# Motors.net
KiCad netlist of a schematic drawn in Altium Designer
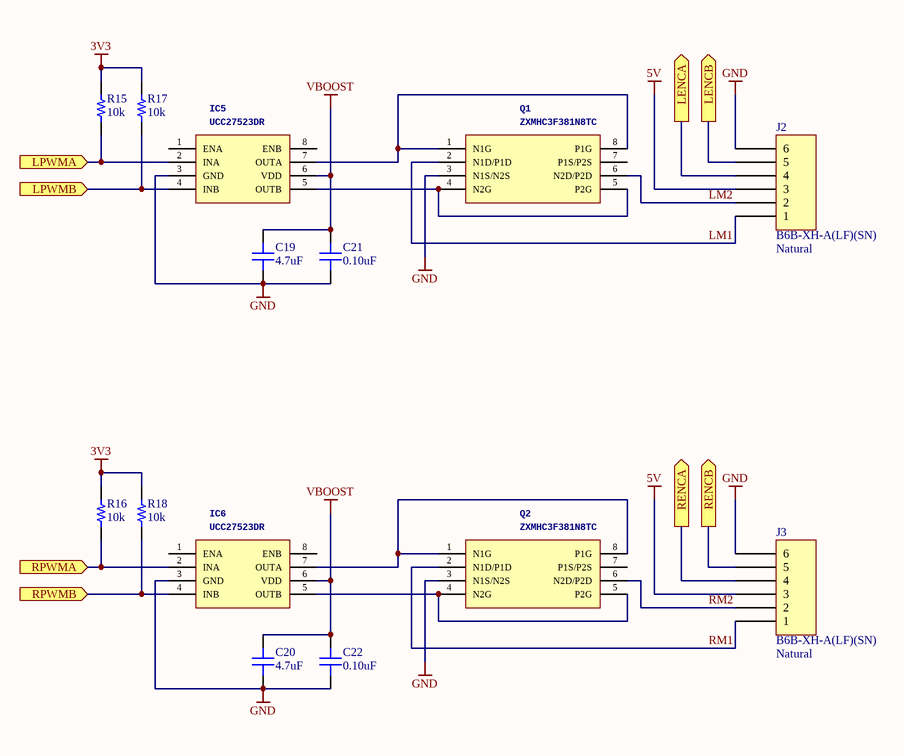
[diagram p0: Motors.SchDoc]

(export (version "E")
  (design (tool "Eeschema 10.0.6"))
  (components
    (comp (ref "C19")
      (value "4.7uF")
      (footprint "CAP 0805/2012")
      (description "CAP CER 4.7UF 10V Y5V 0805")
      (fields (field (name "PART NUMBER") "CC0805ZRY5V6BB475") (field (name "MANUFACTURER") "Yageo"))
      (libsource (lib "Celestial Library Database") (part "Capacitor"))
    )
    (comp (ref "C20")
      (value "4.7uF")
      (footprint "CAP 0805/2012")
      (description "CAP CER 4.7UF 10V Y5V 0805")
      (fields (field (name "PART NUMBER") "CC0805ZRY5V6BB475") (field (name "MANUFACTURER") "Yageo"))
      (libsource (lib "Celestial Library Database") (part "Capacitor"))
    )
    (comp (ref "C21")
      (value "0.10uF")
      (footprint "CAP 0402/1005")
      (description "CAP CER 0.1UF 16V X7R 0402")
      (fields
        (field (name "PART NUMBER") "GCM155R71C104KA55D")
        (field (name "MANUFACTURER") "Murata Electronics North America")
      )
      (libsource (lib "Celestial Library Database") (part "Capacitor"))
    )
    (comp (ref "C22")
      (value "0.10uF")
      (footprint "CAP 0402/1005")
      (description "CAP CER 0.1UF 16V X7R 0402")
      (fields
        (field (name "PART NUMBER") "GCM155R71C104KA55D")
        (field (name "MANUFACTURER") "Murata Electronics North America")
      )
      (libsource (lib "Celestial Library Database") (part "Capacitor"))
    )
    (comp (ref "IC5")
      (value "UCC27523DR")
      (footprint "SOIC127P600X175-8N")
      (fields (field (name "LIBRARYNAME") "micromousev2Parts"))
      (libsource (lib "micromousev2Parts") (part "UCC27523DR"))
    )
    (comp (ref "IC6")
      (value "UCC27523DR")
      (footprint "SOIC127P600X175-8N")
      (fields (field (name "LIBRARYNAME") "micromousev2Parts"))
      (libsource (lib "micromousev2Parts") (part "UCC27523DR"))
    )
    (comp (ref "J2")
      (value "B6B-XH-A(LF)(SN)")
      (footprint "JST XH B6B-XH-A")
      (description "CONN HEADER XH TOP 6POS 2.5MM")
      (fields (field (name "COLOUR") "Natural") (field (name "MANUFACTURER") "JST Sales America Inc."))
      (libsource (lib "Celestial Library Database") (part "6 Pin"))
    )
    (comp (ref "J3")
      (value "B6B-XH-A(LF)(SN)")
      (footprint "JST XH B6B-XH-A")
      (description "CONN HEADER XH TOP 6POS 2.5MM")
      (fields (field (name "COLOUR") "Natural") (field (name "MANUFACTURER") "JST Sales America Inc."))
      (libsource (lib "Celestial Library Database") (part "6 Pin"))
    )
    (comp (ref "Q1")
      (value "ZXMHC3F381N8TC")
      (footprint "SOIC127P600X175-8N")
      (fields (field (name "RS_PART_NUMBER") "7515344P") (field (name "LIBRARYNAME") "micromousev2Parts"))
      (libsource (lib "micromousev2Parts") (part "ZXMHC3F381N8TC"))
    )
    (comp (ref "Q2")
      (value "ZXMHC3F381N8TC")
      (footprint "SOIC127P600X175-8N")
      (fields (field (name "RS_PART_NUMBER") "7515344P") (field (name "LIBRARYNAME") "micromousev2Parts"))
      (libsource (lib "micromousev2Parts") (part "ZXMHC3F381N8TC"))
    )
    (comp (ref "R15")
      (value "10k")
      (footprint "RES 0402/1005")
      (description "RES SMD 10K OHM 1% 1/10W 0402")
      (fields
        (field (name "PART NUMBER") "ERJ-2RKF1002X")
        (field (name "MANUFACTURER") "Panasonic Electronic Components")
      )
      (libsource (lib "Celestial Library Database") (part "Resistor"))
    )
    (comp (ref "R16")
      (value "10k")
      (footprint "RES 0402/1005")
      (description "RES SMD 10K OHM 1% 1/10W 0402")
      (fields
        (field (name "PART NUMBER") "ERJ-2RKF1002X")
        (field (name "MANUFACTURER") "Panasonic Electronic Components")
      )
      (libsource (lib "Celestial Library Database") (part "Resistor"))
    )
    (comp (ref "R17")
      (value "10k")
      (footprint "RES 0402/1005")
      (description "RES SMD 10K OHM 1% 1/10W 0402")
      (fields
        (field (name "PART NUMBER") "ERJ-2RKF1002X")
        (field (name "MANUFACTURER") "Panasonic Electronic Components")
      )
      (libsource (lib "Celestial Library Database") (part "Resistor"))
    )
    (comp (ref "R18")
      (value "10k")
      (footprint "RES 0402/1005")
      (description "RES SMD 10K OHM 1% 1/10W 0402")
      (fields
        (field (name "PART NUMBER") "ERJ-2RKF1002X")
        (field (name "MANUFACTURER") "Panasonic Electronic Components")
      )
      (libsource (lib "Celestial Library Database") (part "Resistor"))
    )
  )
  (nets
    (net (code "1") (name "/LENCA") (class "Default")
      (node (ref "J2") (pin "4") (pinfunction "4_4") (pintype "passive"))
    )
    (net (code "2") (name "/LENCB") (class "Default")
      (node (ref "J2") (pin "5") (pinfunction "5_5") (pintype "passive"))
    )
    (net (code "3") (name "/LM1") (class "Default")
      (node (ref "J2") (pin "1") (pinfunction "1_1") (pintype "passive"))
      (node (ref "Q1") (pin "2") (pinfunction "N1D/P1D_2") (pintype "passive"))
    )
    (net (code "4") (name "/LM2") (class "Default")
      (node (ref "J2") (pin "2") (pinfunction "2_2") (pintype "passive"))
      (node (ref "Q1") (pin "6") (pinfunction "N2D/P2D_6") (pintype "passive"))
    )
    (net (code "5") (name "/LPWMA") (class "Default")
      (node (ref "IC5") (pin "2") (pinfunction "INA_2") (pintype "passive"))
      (node (ref "R15") (pin "1") (pinfunction "1_1") (pintype "passive"))
    )
    (net (code "6") (name "/LPWMB") (class "Default")
      (node (ref "IC5") (pin "4") (pinfunction "INB_4") (pintype "passive"))
      (node (ref "R17") (pin "1") (pinfunction "1_1") (pintype "passive"))
    )
    (net (code "7") (name "/RENCA") (class "Default")
      (node (ref "J3") (pin "4") (pinfunction "4_4") (pintype "passive"))
    )
    (net (code "8") (name "/RENCB") (class "Default")
      (node (ref "J3") (pin "5") (pinfunction "5_5") (pintype "passive"))
    )
    (net (code "9") (name "/RM1") (class "Default")
      (node (ref "J3") (pin "1") (pinfunction "1_1") (pintype "passive"))
      (node (ref "Q2") (pin "2") (pinfunction "N1D/P1D_2") (pintype "passive"))
    )
    (net (code "10") (name "/RM2") (class "Default")
      (node (ref "J3") (pin "2") (pinfunction "2_2") (pintype "passive"))
      (node (ref "Q2") (pin "6") (pinfunction "N2D/P2D_6") (pintype "passive"))
    )
    (net (code "11") (name "/RPWMA") (class "Default")
      (node (ref "IC6") (pin "2") (pinfunction "INA_2") (pintype "passive"))
      (node (ref "R16") (pin "1") (pinfunction "1_1") (pintype "passive"))
    )
    (net (code "12") (name "/RPWMB") (class "Default")
      (node (ref "IC6") (pin "4") (pinfunction "INB_4") (pintype "passive"))
      (node (ref "R18") (pin "1") (pinfunction "1_1") (pintype "passive"))
    )
    (net (code "13") (name "3V3") (class "Default")
      (node (ref "R15") (pin "2") (pinfunction "2_2") (pintype "passive"))
      (node (ref "R16") (pin "2") (pinfunction "2_2") (pintype "passive"))
      (node (ref "R17") (pin "2") (pinfunction "2_2") (pintype "passive"))
      (node (ref "R18") (pin "2") (pinfunction "2_2") (pintype "passive"))
    )
    (net (code "14") (name "5V") (class "Default")
      (node (ref "J2") (pin "3") (pinfunction "3_3") (pintype "passive"))
      (node (ref "J3") (pin "3") (pinfunction "3_3") (pintype "passive"))
    )
    (net (code "15") (name "GND") (class "Default")
      (node (ref "C19") (pin "1") (pinfunction "1_1") (pintype "passive"))
      (node (ref "C20") (pin "1") (pinfunction "1_1") (pintype "passive"))
      (node (ref "C21") (pin "1") (pinfunction "1_1") (pintype "passive"))
      (node (ref "C22") (pin "1") (pinfunction "1_1") (pintype "passive"))
      (node (ref "IC5") (pin "3") (pinfunction "GND_3") (pintype "passive"))
      (node (ref "IC6") (pin "3") (pinfunction "GND_3") (pintype "passive"))
      (node (ref "J2") (pin "6") (pinfunction "6_6") (pintype "passive"))
      (node (ref "J3") (pin "6") (pinfunction "6_6") (pintype "passive"))
      (node (ref "Q1") (pin "3") (pinfunction "N1S/N2S_3") (pintype "passive"))
      (node (ref "Q2") (pin "3") (pinfunction "N1S/N2S_3") (pintype "passive"))
    )
    (net (code "16") (name "Net-(IC5-OUTA)") (class "Default")
      (node (ref "IC5") (pin "7") (pinfunction "OUTA_7") (pintype "passive"))
      (node (ref "Q1") (pin "1") (pinfunction "N1G_1") (pintype "passive"))
      (node (ref "Q1") (pin "8") (pinfunction "P1G_8") (pintype "passive"))
    )
    (net (code "17") (name "Net-(IC5-OUTB)") (class "Default")
      (node (ref "IC5") (pin "5") (pinfunction "OUTB_5") (pintype "passive"))
      (node (ref "Q1") (pin "4") (pinfunction "N2G_4") (pintype "passive"))
      (node (ref "Q1") (pin "5") (pinfunction "P2G_5") (pintype "passive"))
    )
    (net (code "18") (name "Net-(IC6-OUTA)") (class "Default")
      (node (ref "IC6") (pin "7") (pinfunction "OUTA_7") (pintype "passive"))
      (node (ref "Q2") (pin "1") (pinfunction "N1G_1") (pintype "passive"))
      (node (ref "Q2") (pin "8") (pinfunction "P1G_8") (pintype "passive"))
    )
    (net (code "19") (name "Net-(IC6-OUTB)") (class "Default")
      (node (ref "IC6") (pin "5") (pinfunction "OUTB_5") (pintype "passive"))
      (node (ref "Q2") (pin "4") (pinfunction "N2G_4") (pintype "passive"))
      (node (ref "Q2") (pin "5") (pinfunction "P2G_5") (pintype "passive"))
    )
    (net (code "20") (name "VBOOST") (class "Default")
      (node (ref "C19") (pin "2") (pinfunction "2_2") (pintype "passive"))
      (node (ref "C20") (pin "2") (pinfunction "2_2") (pintype "passive"))
      (node (ref "C21") (pin "2") (pinfunction "2_2") (pintype "passive"))
      (node (ref "C22") (pin "2") (pinfunction "2_2") (pintype "passive"))
      (node (ref "IC5") (pin "6") (pinfunction "VDD_6") (pintype "passive"))
      (node (ref "IC6") (pin "6") (pinfunction "VDD_6") (pintype "passive"))
    )
    (net (code "21") (name "unconnected-(IC5-ENA-Pad1)") (class "Default")
      (node (ref "IC5") (pin "1") (pinfunction "ENA_1") (pintype "passive"))
    )
    (net (code "22") (name "unconnected-(IC5-ENB-Pad8)") (class "Default")
      (node (ref "IC5") (pin "8") (pinfunction "ENB_8") (pintype "passive"))
    )
    (net (code "23") (name "unconnected-(IC6-ENA-Pad1)") (class "Default")
      (node (ref "IC6") (pin "1") (pinfunction "ENA_1") (pintype "passive"))
    )
    (net (code "24") (name "unconnected-(IC6-ENB-Pad8)") (class "Default")
      (node (ref "IC6") (pin "8") (pinfunction "ENB_8") (pintype "passive"))
    )
    (net (code "25") (name "unconnected-(Q1-P1S{slash}P2S-Pad7)") (class "Default")
      (node (ref "Q1") (pin "7") (pinfunction "P1S/P2S_7") (pintype "passive"))
    )
    (net (code "26") (name "unconnected-(Q2-P1S{slash}P2S-Pad7)") (class "Default")
      (node (ref "Q2") (pin "7") (pinfunction "P1S/P2S_7") (pintype "passive"))
    )
  )
)
